# Interface.net
KiCad netlist of a schematic drawn in Altium Designer
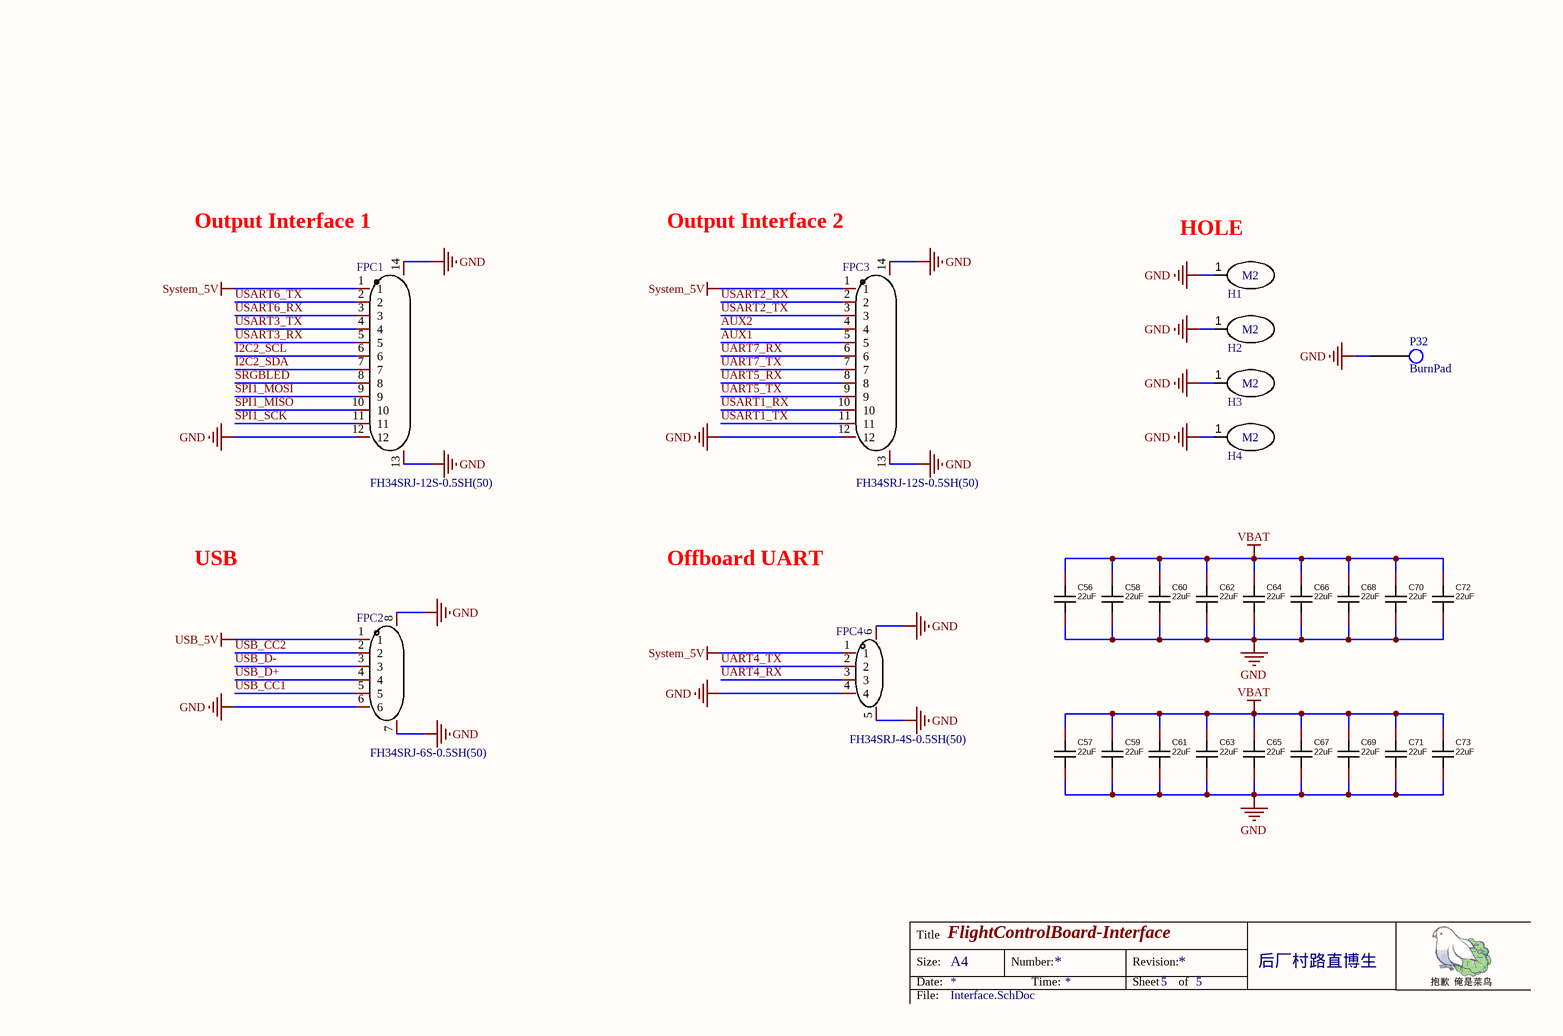
[diagram p0: Interface.SchDoc]

(export (version "E")
  (design (tool "Eeschema 10.0.6"))
  (components
    (comp (ref "C56")
      (value "22uF")
      (footprint "C0805")
      (libsource (lib "Capacitor") (part "CC0603KRX7R9BB104"))
    )
    (comp (ref "C57")
      (value "22uF")
      (footprint "C0805")
      (libsource (lib "Capacitor") (part "CC0603KRX7R9BB104"))
    )
    (comp (ref "C58")
      (value "22uF")
      (footprint "C0805")
      (libsource (lib "Capacitor") (part "CC0603KRX7R9BB104"))
    )
    (comp (ref "C59")
      (value "22uF")
      (footprint "C0805")
      (libsource (lib "Capacitor") (part "CC0603KRX7R9BB104"))
    )
    (comp (ref "C60")
      (value "22uF")
      (footprint "C0805")
      (libsource (lib "Capacitor") (part "CC0603KRX7R9BB104"))
    )
    (comp (ref "C61")
      (value "22uF")
      (footprint "C0805")
      (libsource (lib "Capacitor") (part "CC0603KRX7R9BB104"))
    )
    (comp (ref "C62")
      (value "22uF")
      (footprint "C0805")
      (libsource (lib "Capacitor") (part "CC0603KRX7R9BB104"))
    )
    (comp (ref "C63")
      (value "22uF")
      (footprint "C0805")
      (libsource (lib "Capacitor") (part "CC0603KRX7R9BB104"))
    )
    (comp (ref "C64")
      (value "22uF")
      (footprint "C0805")
      (libsource (lib "Capacitor") (part "CC0603KRX7R9BB104"))
    )
    (comp (ref "C65")
      (value "22uF")
      (footprint "C0805")
      (libsource (lib "Capacitor") (part "CC0603KRX7R9BB104"))
    )
    (comp (ref "C66")
      (value "22uF")
      (footprint "C0805")
      (libsource (lib "Capacitor") (part "CC0603KRX7R9BB104"))
    )
    (comp (ref "C67")
      (value "22uF")
      (footprint "C0805")
      (libsource (lib "Capacitor") (part "CC0603KRX7R9BB104"))
    )
    (comp (ref "C68")
      (value "22uF")
      (footprint "C0805")
      (libsource (lib "Capacitor") (part "CC0603KRX7R9BB104"))
    )
    (comp (ref "C69")
      (value "22uF")
      (footprint "C0805")
      (libsource (lib "Capacitor") (part "CC0603KRX7R9BB104"))
    )
    (comp (ref "C70")
      (value "22uF")
      (footprint "C0805")
      (libsource (lib "Capacitor") (part "CC0603KRX7R9BB104"))
    )
    (comp (ref "C71")
      (value "22uF")
      (footprint "C0805")
      (libsource (lib "Capacitor") (part "CC0603KRX7R9BB104"))
    )
    (comp (ref "C72")
      (value "22uF")
      (footprint "C0805")
      (libsource (lib "Capacitor") (part "CC0603KRX7R9BB104"))
    )
    (comp (ref "C73")
      (value "22uF")
      (footprint "C0805")
      (libsource (lib "Capacitor") (part "CC0603KRX7R9BB104"))
    )
    (comp (ref "FPC1")
      (value "FH34SRJ-12S-0.5SH(50)")
      (footprint "FFC-SMD_12P-P0.50_FH34SRJ-12S-0.5SH")
      (fields (field (name "MANUFACTURER") "HRS(广濑)"))
      (libsource (lib "FPC") (part "FH34SRJ-12S-0.5SH(50)"))
    )
    (comp (ref "FPC2")
      (value "FH34SRJ-6S-0.5SH(50)")
      (footprint "FFC-SMD_6P-P0.50_FH34SRJ-6S-0.5SH")
      (fields (field (name "MANUFACTURER") "HRS(广濑)"))
      (libsource (lib "FPC") (part "FH34SRJ-6S-0.5SH(50)"))
    )
    (comp (ref "FPC3")
      (value "FH34SRJ-12S-0.5SH(50)")
      (footprint "FFC-SMD_12P-P0.50_FH34SRJ-12S-0.5SH")
      (fields (field (name "MANUFACTURER") "HRS(广濑)"))
      (libsource (lib "FPC") (part "FH34SRJ-12S-0.5SH(50)"))
    )
    (comp (ref "FPC4")
      (value "FH34SRJ-4S-0.5SH(50)")
      (footprint "FFC-SMD_4P-P0.50_FH34SRJ-4S-0.5SH")
      (fields (field (name "MANUFACTURER") "HRS(广濑)"))
      (libsource (lib "FPC") (part "FH34SRJ-4S-0.5SH(50)"))
    )
    (comp (ref "H1") (value "M2_HOLE") (footprint "M2_HOLE") (libsource (lib "HOLE") (part "M2_HOLE")))
    (comp (ref "H2") (value "M2_HOLE") (footprint "M2_HOLE") (libsource (lib "HOLE") (part "M2_HOLE")))
    (comp (ref "H3") (value "M2_HOLE") (footprint "M2_HOLE") (libsource (lib "HOLE") (part "M2_HOLE")))
    (comp (ref "H4") (value "M2_HOLE") (footprint "M2_HOLE") (libsource (lib "HOLE") (part "M2_HOLE")))
    (comp (ref "P32") (value "BurnPad") (footprint "BurnPad_0.5mm") (libsource (lib "Pad") (part "BurnPad")))
  )
  (nets
    (net (code "1") (name "/AUX1") (class "Default")
      (node (ref "FPC3") (pin "5") (pinfunction "5_5") (pintype "passive"))
    )
    (net (code "2") (name "/AUX2") (class "Default")
      (node (ref "FPC3") (pin "4") (pinfunction "4_4") (pintype "passive"))
    )
    (net (code "3") (name "/I2C2_SCL") (class "Default")
      (node (ref "FPC1") (pin "6") (pinfunction "6_6") (pintype "passive"))
    )
    (net (code "4") (name "/I2C2_SDA") (class "Default")
      (node (ref "FPC1") (pin "7") (pinfunction "7_7") (pintype "passive"))
    )
    (net (code "5") (name "/SPI1_MISO") (class "Default")
      (node (ref "FPC1") (pin "10") (pinfunction "10_10") (pintype "passive"))
    )
    (net (code "6") (name "/SPI1_MOSI") (class "Default")
      (node (ref "FPC1") (pin "9") (pinfunction "9_9") (pintype "passive"))
    )
    (net (code "7") (name "/SPI1_SCK") (class "Default")
      (node (ref "FPC1") (pin "11") (pinfunction "11_11") (pintype "passive"))
    )
    (net (code "8") (name "/SRGBLED") (class "Default")
      (node (ref "FPC1") (pin "8") (pinfunction "8_8") (pintype "passive"))
    )
    (net (code "9") (name "/UART4_RX") (class "Default")
      (node (ref "FPC4") (pin "3") (pinfunction "3_3") (pintype "passive"))
    )
    (net (code "10") (name "/UART4_TX") (class "Default")
      (node (ref "FPC4") (pin "2") (pinfunction "2_2") (pintype "passive"))
    )
    (net (code "11") (name "/UART5_RX") (class "Default")
      (node (ref "FPC3") (pin "8") (pinfunction "8_8") (pintype "passive"))
    )
    (net (code "12") (name "/UART5_TX") (class "Default")
      (node (ref "FPC3") (pin "9") (pinfunction "9_9") (pintype "passive"))
    )
    (net (code "13") (name "/UART7_RX") (class "Default")
      (node (ref "FPC3") (pin "6") (pinfunction "6_6") (pintype "passive"))
    )
    (net (code "14") (name "/UART7_TX") (class "Default")
      (node (ref "FPC3") (pin "7") (pinfunction "7_7") (pintype "passive"))
    )
    (net (code "15") (name "/USART1_RX") (class "Default")
      (node (ref "FPC3") (pin "10") (pinfunction "10_10") (pintype "passive"))
    )
    (net (code "16") (name "/USART1_TX") (class "Default")
      (node (ref "FPC3") (pin "11") (pinfunction "11_11") (pintype "passive"))
    )
    (net (code "17") (name "/USART2_RX") (class "Default")
      (node (ref "FPC3") (pin "2") (pinfunction "2_2") (pintype "passive"))
    )
    (net (code "18") (name "/USART2_TX") (class "Default")
      (node (ref "FPC3") (pin "3") (pinfunction "3_3") (pintype "passive"))
    )
    (net (code "19") (name "/USART3_RX") (class "Default")
      (node (ref "FPC1") (pin "5") (pinfunction "5_5") (pintype "passive"))
    )
    (net (code "20") (name "/USART3_TX") (class "Default")
      (node (ref "FPC1") (pin "4") (pinfunction "4_4") (pintype "passive"))
    )
    (net (code "21") (name "/USART6_RX") (class "Default")
      (node (ref "FPC1") (pin "3") (pinfunction "3_3") (pintype "passive"))
    )
    (net (code "22") (name "/USART6_TX") (class "Default")
      (node (ref "FPC1") (pin "2") (pinfunction "2_2") (pintype "passive"))
    )
    (net (code "23") (name "/USB_CC1") (class "Default")
      (node (ref "FPC2") (pin "5") (pinfunction "5_5") (pintype "passive"))
    )
    (net (code "24") (name "/USB_CC2") (class "Default")
      (node (ref "FPC2") (pin "2") (pinfunction "2_2") (pintype "passive"))
    )
    (net (code "25") (name "/USB_D+") (class "Default")
      (node (ref "FPC2") (pin "4") (pinfunction "4_4") (pintype "passive"))
    )
    (net (code "26") (name "/USB_D-") (class "Default")
      (node (ref "FPC2") (pin "3") (pinfunction "3_3") (pintype "passive"))
    )
    (net (code "27") (name "GND") (class "Default")
      (node (ref "C56") (pin "2") (pinfunction "2_2") (pintype "passive"))
      (node (ref "C57") (pin "2") (pinfunction "2_2") (pintype "passive"))
      (node (ref "C58") (pin "2") (pinfunction "2_2") (pintype "passive"))
      (node (ref "C59") (pin "2") (pinfunction "2_2") (pintype "passive"))
      (node (ref "C60") (pin "2") (pinfunction "2_2") (pintype "passive"))
      (node (ref "C61") (pin "2") (pinfunction "2_2") (pintype "passive"))
      (node (ref "C62") (pin "2") (pinfunction "2_2") (pintype "passive"))
      (node (ref "C63") (pin "2") (pinfunction "2_2") (pintype "passive"))
      (node (ref "C64") (pin "2") (pinfunction "2_2") (pintype "passive"))
      (node (ref "C65") (pin "2") (pinfunction "2_2") (pintype "passive"))
      (node (ref "C66") (pin "2") (pinfunction "2_2") (pintype "passive"))
      (node (ref "C67") (pin "2") (pinfunction "2_2") (pintype "passive"))
      (node (ref "C68") (pin "2") (pinfunction "2_2") (pintype "passive"))
      (node (ref "C69") (pin "2") (pinfunction "2_2") (pintype "passive"))
      (node (ref "C70") (pin "2") (pinfunction "2_2") (pintype "passive"))
      (node (ref "C71") (pin "2") (pinfunction "2_2") (pintype "passive"))
      (node (ref "C72") (pin "2") (pinfunction "2_2") (pintype "passive"))
      (node (ref "C73") (pin "2") (pinfunction "2_2") (pintype "passive"))
      (node (ref "FPC1") (pin "12") (pinfunction "12_12") (pintype "passive"))
      (node (ref "FPC1") (pin "13") (pinfunction "13_13") (pintype "passive"))
      (node (ref "FPC1") (pin "14") (pinfunction "14_14") (pintype "passive"))
      (node (ref "FPC2") (pin "6") (pinfunction "6_6") (pintype "passive"))
      (node (ref "FPC2") (pin "7") (pinfunction "7_7") (pintype "passive"))
      (node (ref "FPC2") (pin "8") (pinfunction "8_8") (pintype "passive"))
      (node (ref "FPC3") (pin "12") (pinfunction "12_12") (pintype "passive"))
      (node (ref "FPC3") (pin "13") (pinfunction "13_13") (pintype "passive"))
      (node (ref "FPC3") (pin "14") (pinfunction "14_14") (pintype "passive"))
      (node (ref "FPC4") (pin "4") (pinfunction "4_4") (pintype "passive"))
      (node (ref "FPC4") (pin "5") (pinfunction "5_5") (pintype "passive"))
      (node (ref "FPC4") (pin "6") (pinfunction "6_6") (pintype "passive"))
      (node (ref "H1") (pin "1") (pinfunction "1_1") (pintype "passive"))
      (node (ref "H2") (pin "1") (pinfunction "1_1") (pintype "passive"))
      (node (ref "H3") (pin "1") (pinfunction "1_1") (pintype "passive"))
      (node (ref "H4") (pin "1") (pinfunction "1_1") (pintype "passive"))
      (node (ref "P32") (pin "1") (pinfunction "1_1") (pintype "passive"))
    )
    (net (code "28") (name "System_5V") (class "Default")
      (node (ref "FPC1") (pin "1") (pinfunction "1_1") (pintype "passive"))
      (node (ref "FPC3") (pin "1") (pinfunction "1_1") (pintype "passive"))
      (node (ref "FPC4") (pin "1") (pinfunction "1_1") (pintype "passive"))
    )
    (net (code "29") (name "USB_5V") (class "Default")
      (node (ref "FPC2") (pin "1") (pinfunction "1_1") (pintype "passive"))
    )
    (net (code "30") (name "VBAT") (class "Default")
      (node (ref "C56") (pin "1") (pinfunction "1_1") (pintype "passive"))
      (node (ref "C57") (pin "1") (pinfunction "1_1") (pintype "passive"))
      (node (ref "C58") (pin "1") (pinfunction "1_1") (pintype "passive"))
      (node (ref "C59") (pin "1") (pinfunction "1_1") (pintype "passive"))
      (node (ref "C60") (pin "1") (pinfunction "1_1") (pintype "passive"))
      (node (ref "C61") (pin "1") (pinfunction "1_1") (pintype "passive"))
      (node (ref "C62") (pin "1") (pinfunction "1_1") (pintype "passive"))
      (node (ref "C63") (pin "1") (pinfunction "1_1") (pintype "passive"))
      (node (ref "C64") (pin "1") (pinfunction "1_1") (pintype "passive"))
      (node (ref "C65") (pin "1") (pinfunction "1_1") (pintype "passive"))
      (node (ref "C66") (pin "1") (pinfunction "1_1") (pintype "passive"))
      (node (ref "C67") (pin "1") (pinfunction "1_1") (pintype "passive"))
      (node (ref "C68") (pin "1") (pinfunction "1_1") (pintype "passive"))
      (node (ref "C69") (pin "1") (pinfunction "1_1") (pintype "passive"))
      (node (ref "C70") (pin "1") (pinfunction "1_1") (pintype "passive"))
      (node (ref "C71") (pin "1") (pinfunction "1_1") (pintype "passive"))
      (node (ref "C72") (pin "1") (pinfunction "1_1") (pintype "passive"))
      (node (ref "C73") (pin "1") (pinfunction "1_1") (pintype "passive"))
    )
  )
)
